# RasPi-BplusHAT.net
KiCad netlist of a schematic drawn in EAGLE
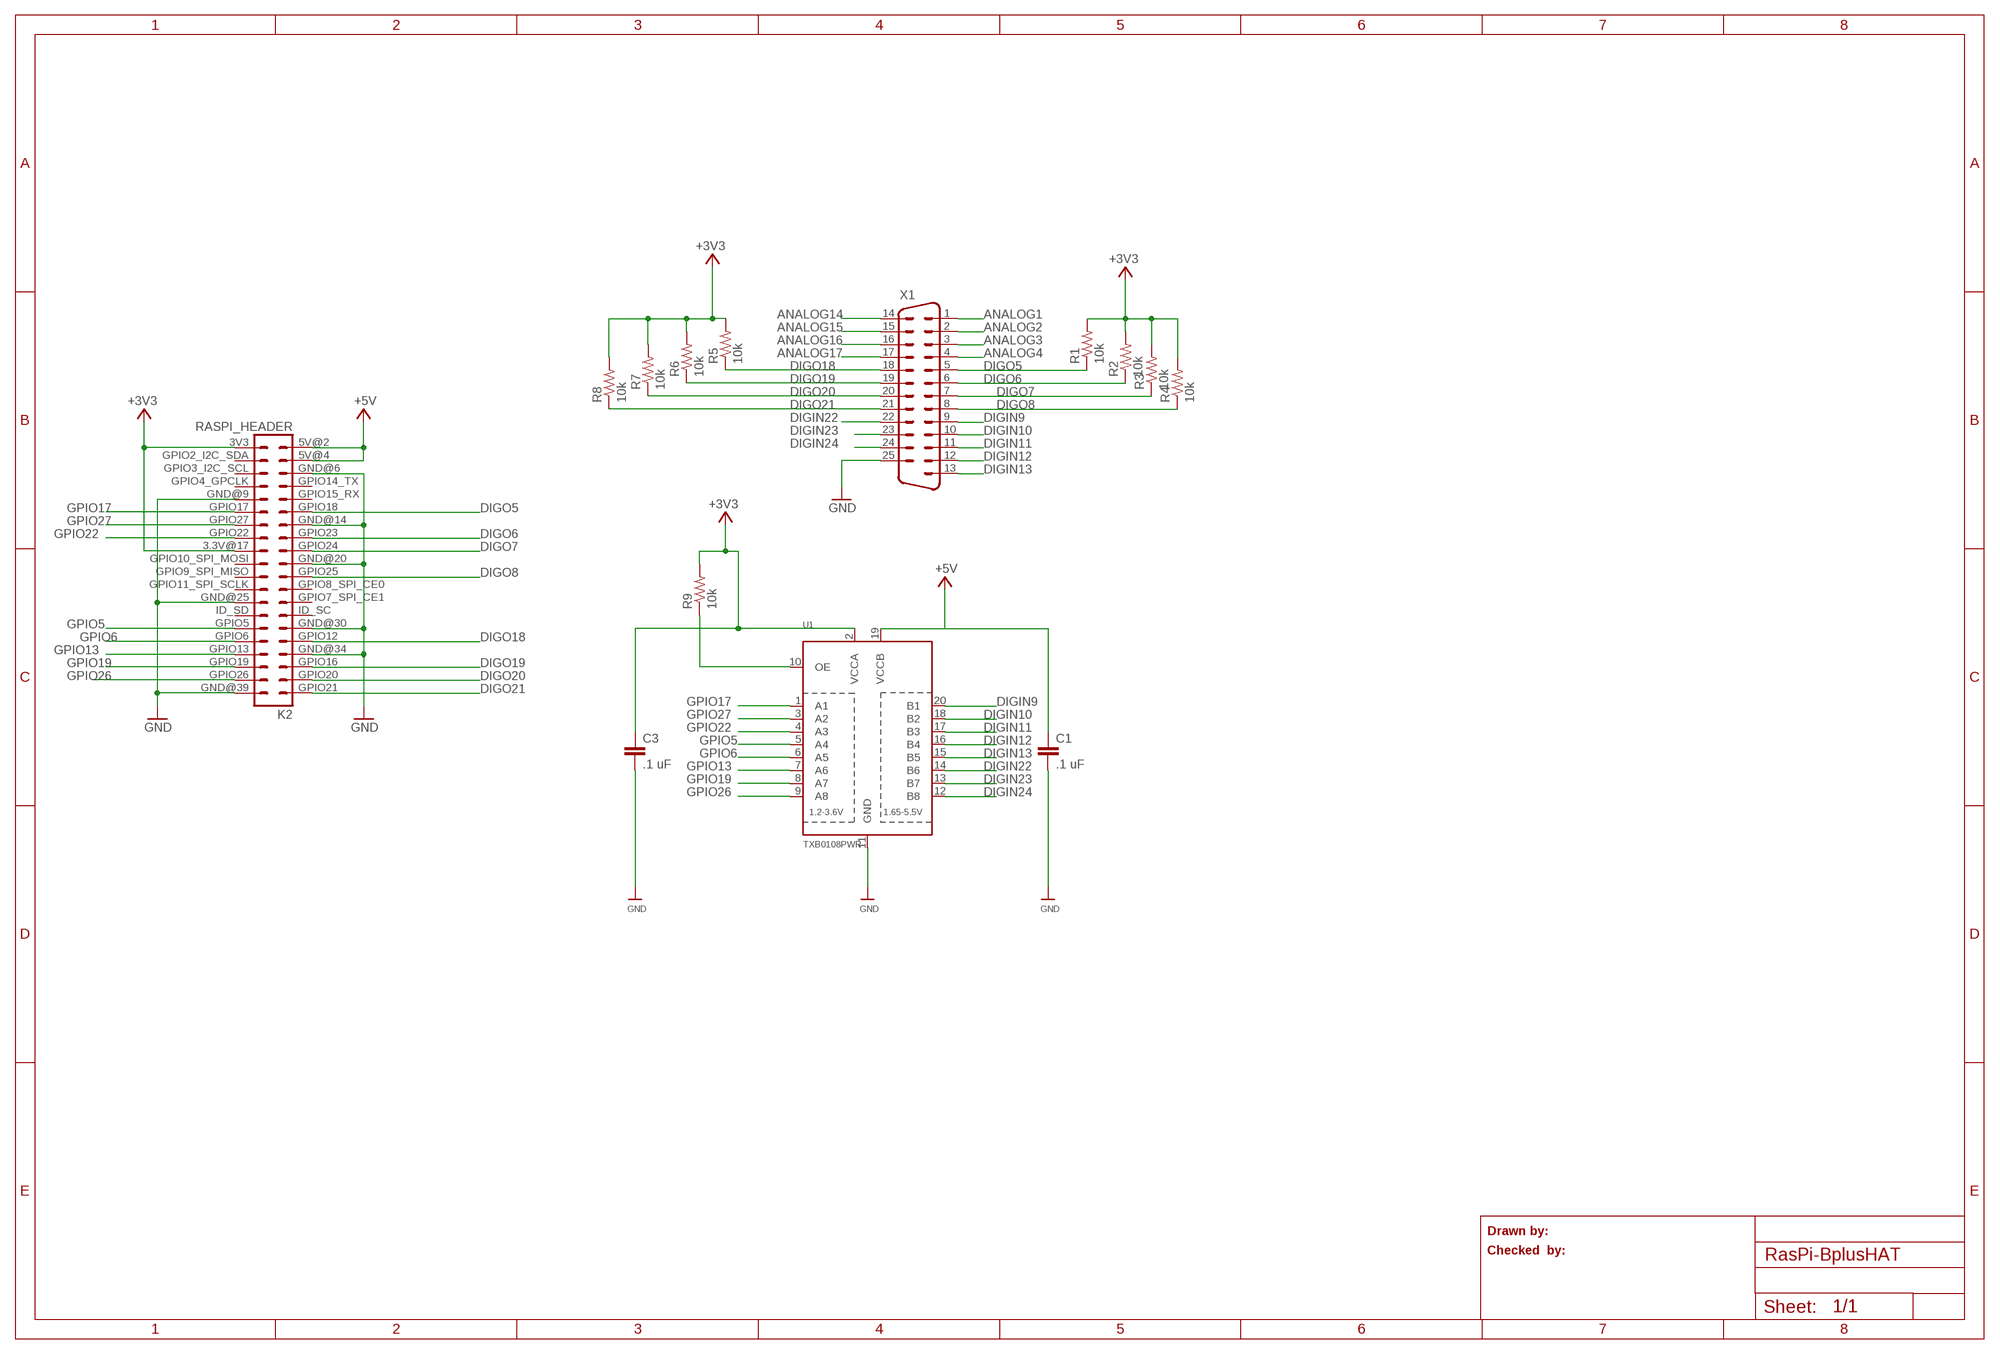
[diagram p0: schematic, sheet 1]

(export (version "E")
  (design (tool "Eeschema 10.0.6"))
  (components
    (comp (ref "C1")
      (value ".1 uF")
      (footprint "eagle-import:CAP-PTH-SMALL-KIT")
      (libsource (lib "eagle-import") (part "0.1UF-50V-20%(PTH)KIT-EZ"))
    )
    (comp (ref "C3")
      (value ".1 uF")
      (footprint "eagle-import:CAP-PTH-SMALL-KIT")
      (libsource (lib "eagle-import") (part "0.1UF-50V-20%(PTH)KIT-EZ"))
    )
    (comp (ref "K2")
      (value "RASPI_HEADER")
      (footprint "eagle-import:RASPI_HEADER")
      (libsource (lib "eagle-import") (part "RASPI_HEADER"))
    )
    (comp (ref "R1")
      (value "10k")
      (footprint "eagle-import:0207_10")
      (libsource (lib "eagle-import") (part "R-US_0207/10"))
    )
    (comp (ref "R2")
      (value "10k")
      (footprint "eagle-import:0207_10")
      (libsource (lib "eagle-import") (part "R-US_0207/10"))
    )
    (comp (ref "R3")
      (value "10k")
      (footprint "eagle-import:0207_10")
      (libsource (lib "eagle-import") (part "R-US_0207/10"))
    )
    (comp (ref "R4")
      (value "10k")
      (footprint "eagle-import:0207_10")
      (libsource (lib "eagle-import") (part "R-US_0207/10"))
    )
    (comp (ref "R5")
      (value "10k")
      (footprint "eagle-import:0207_10")
      (libsource (lib "eagle-import") (part "R-US_0207/10"))
    )
    (comp (ref "R6")
      (value "10k")
      (footprint "eagle-import:0207_10")
      (libsource (lib "eagle-import") (part "R-US_0207/10"))
    )
    (comp (ref "R7")
      (value "10k")
      (footprint "eagle-import:0207_10")
      (libsource (lib "eagle-import") (part "R-US_0207/10"))
    )
    (comp (ref "R8")
      (value "10k")
      (footprint "eagle-import:0207_10")
      (libsource (lib "eagle-import") (part "R-US_0207/10"))
    )
    (comp (ref "R9")
      (value "10k")
      (footprint "eagle-import:0207_10")
      (libsource (lib "eagle-import") (part "R-US_0207/10"))
    )
    (comp (ref "U1")
      (value "TXB0108PWR")
      (footprint "eagle-import:TSSOP20")
      (libsource (lib "eagle-import") (part "TXB0108PWR"))
    )
    (comp (ref "X1")
      (value "M25HP")
      (footprint "eagle-import:M25HP")
      (libsource (lib "eagle-import") (part "M25HP"))
    )
  )
  (nets
    (net (code "1") (name "+3V3") (class "Default")
      (node (ref "C3") (pin "1") (pinfunction "1_1") (pintype "passive"))
      (node (ref "K2") (pin "3.3V@17") (pinfunction "17_3.3V@17") (pintype "passive"))
      (node (ref "K2") (pin "3V3") (pinfunction "1_3V3") (pintype "passive"))
      (node (ref "R1") (pin "2") (pinfunction "2_2") (pintype "passive"))
      (node (ref "R2") (pin "2") (pinfunction "2_2") (pintype "passive"))
      (node (ref "R3") (pin "2") (pinfunction "2_2") (pintype "passive"))
      (node (ref "R4") (pin "2") (pinfunction "2_2") (pintype "passive"))
      (node (ref "R5") (pin "2") (pinfunction "2_2") (pintype "passive"))
      (node (ref "R6") (pin "2") (pinfunction "2_2") (pintype "passive"))
      (node (ref "R7") (pin "2") (pinfunction "2_2") (pintype "passive"))
      (node (ref "R8") (pin "2") (pinfunction "2_2") (pintype "passive"))
      (node (ref "R9") (pin "2") (pinfunction "2_2") (pintype "passive"))
      (node (ref "U1") (pin "2") (pinfunction "VCCA_2") (pintype "bidirectional"))
    )
    (net (code "2") (name "+5V") (class "Default")
      (node (ref "C1") (pin "1") (pinfunction "1_1") (pintype "passive"))
      (node (ref "K2") (pin "5V@2") (pinfunction "2_5V@2") (pintype "passive"))
      (node (ref "K2") (pin "5V@4") (pinfunction "4_5V@4") (pintype "passive"))
      (node (ref "U1") (pin "19") (pinfunction "VCCB_19") (pintype "bidirectional"))
    )
    (net (code "3") (name "/ANALOG1") (class "Default")
      (node (ref "X1") (pin "1") (pinfunction "1_1") (pintype "passive"))
    )
    (net (code "4") (name "/ANALOG2") (class "Default")
      (node (ref "X1") (pin "2") (pinfunction "2_2") (pintype "passive"))
    )
    (net (code "5") (name "/ANALOG3") (class "Default")
      (node (ref "X1") (pin "3") (pinfunction "3_3") (pintype "passive"))
    )
    (net (code "6") (name "/ANALOG4") (class "Default")
      (node (ref "X1") (pin "4") (pinfunction "4_4") (pintype "passive"))
    )
    (net (code "7") (name "/ANALOG14") (class "Default")
      (node (ref "X1") (pin "14") (pinfunction "14_14") (pintype "passive"))
    )
    (net (code "8") (name "/ANALOG15") (class "Default")
      (node (ref "X1") (pin "15") (pinfunction "15_15") (pintype "passive"))
    )
    (net (code "9") (name "/ANALOG16") (class "Default")
      (node (ref "X1") (pin "16") (pinfunction "16_16") (pintype "passive"))
    )
    (net (code "10") (name "/ANALOG17") (class "Default")
      (node (ref "X1") (pin "17") (pinfunction "17_17") (pintype "passive"))
    )
    (net (code "11") (name "/DIGIN9") (class "Default")
      (node (ref "U1") (pin "20") (pinfunction "B1_20") (pintype "bidirectional"))
      (node (ref "X1") (pin "9") (pinfunction "9_9") (pintype "passive"))
    )
    (net (code "12") (name "/DIGIN10") (class "Default")
      (node (ref "U1") (pin "18") (pinfunction "B2_18") (pintype "bidirectional"))
      (node (ref "X1") (pin "10") (pinfunction "10_10") (pintype "passive"))
    )
    (net (code "13") (name "/DIGIN11") (class "Default")
      (node (ref "U1") (pin "17") (pinfunction "B3_17") (pintype "bidirectional"))
      (node (ref "X1") (pin "11") (pinfunction "11_11") (pintype "passive"))
    )
    (net (code "14") (name "/DIGIN12") (class "Default")
      (node (ref "U1") (pin "16") (pinfunction "B4_16") (pintype "bidirectional"))
      (node (ref "X1") (pin "12") (pinfunction "12_12") (pintype "passive"))
    )
    (net (code "15") (name "/DIGIN13") (class "Default")
      (node (ref "U1") (pin "15") (pinfunction "B5_15") (pintype "bidirectional"))
      (node (ref "X1") (pin "13") (pinfunction "13_13") (pintype "passive"))
    )
    (net (code "16") (name "/DIGIN22") (class "Default")
      (node (ref "U1") (pin "14") (pinfunction "B6_14") (pintype "bidirectional"))
      (node (ref "X1") (pin "22") (pinfunction "22_22") (pintype "passive"))
    )
    (net (code "17") (name "/DIGIN23") (class "Default")
      (node (ref "U1") (pin "13") (pinfunction "B7_13") (pintype "bidirectional"))
      (node (ref "X1") (pin "23") (pinfunction "23_23") (pintype "passive"))
    )
    (net (code "18") (name "/DIGIN24") (class "Default")
      (node (ref "U1") (pin "12") (pinfunction "B8_12") (pintype "bidirectional"))
      (node (ref "X1") (pin "24") (pinfunction "24_24") (pintype "passive"))
    )
    (net (code "19") (name "/DIGO5") (class "Default")
      (node (ref "K2") (pin "GPIO18") (pinfunction "12_GPIO18") (pintype "passive"))
      (node (ref "R1") (pin "1") (pinfunction "1_1") (pintype "passive"))
      (node (ref "X1") (pin "5") (pinfunction "5_5") (pintype "passive"))
    )
    (net (code "20") (name "/DIGO6") (class "Default")
      (node (ref "K2") (pin "GPIO23") (pinfunction "16_GPIO23") (pintype "passive"))
      (node (ref "R2") (pin "1") (pinfunction "1_1") (pintype "passive"))
      (node (ref "X1") (pin "6") (pinfunction "6_6") (pintype "passive"))
    )
    (net (code "21") (name "/DIGO7") (class "Default")
      (node (ref "K2") (pin "GPIO24") (pinfunction "18_GPIO24") (pintype "passive"))
      (node (ref "R3") (pin "1") (pinfunction "1_1") (pintype "passive"))
      (node (ref "X1") (pin "7") (pinfunction "7_7") (pintype "passive"))
    )
    (net (code "22") (name "/DIGO8") (class "Default")
      (node (ref "K2") (pin "GPIO25") (pinfunction "22_GPIO25") (pintype "passive"))
      (node (ref "R4") (pin "1") (pinfunction "1_1") (pintype "passive"))
      (node (ref "X1") (pin "8") (pinfunction "8_8") (pintype "passive"))
    )
    (net (code "23") (name "/DIGO18") (class "Default")
      (node (ref "K2") (pin "GPIO12") (pinfunction "32_GPIO12") (pintype "passive"))
      (node (ref "R5") (pin "1") (pinfunction "1_1") (pintype "passive"))
      (node (ref "X1") (pin "18") (pinfunction "18_18") (pintype "passive"))
    )
    (net (code "24") (name "/DIGO19") (class "Default")
      (node (ref "K2") (pin "GPIO16") (pinfunction "36_GPIO16") (pintype "passive"))
      (node (ref "R6") (pin "1") (pinfunction "1_1") (pintype "passive"))
      (node (ref "X1") (pin "19") (pinfunction "19_19") (pintype "passive"))
    )
    (net (code "25") (name "/DIGO20") (class "Default")
      (node (ref "K2") (pin "GPIO20") (pinfunction "38_GPIO20") (pintype "passive"))
      (node (ref "R7") (pin "1") (pinfunction "1_1") (pintype "passive"))
      (node (ref "X1") (pin "20") (pinfunction "20_20") (pintype "passive"))
    )
    (net (code "26") (name "/DIGO21") (class "Default")
      (node (ref "K2") (pin "GPIO21") (pinfunction "GPIO21_GPIO21") (pintype "passive"))
      (node (ref "R8") (pin "1") (pinfunction "1_1") (pintype "passive"))
      (node (ref "X1") (pin "21") (pinfunction "21_21") (pintype "passive"))
    )
    (net (code "27") (name "/GPIO5") (class "Default")
      (node (ref "K2") (pin "GPIO5") (pinfunction "29_GPIO5") (pintype "passive"))
      (node (ref "U1") (pin "5") (pinfunction "A4_5") (pintype "bidirectional"))
    )
    (net (code "28") (name "/GPIO6") (class "Default")
      (node (ref "K2") (pin "GPIO6") (pinfunction "31_GPIO6") (pintype "passive"))
      (node (ref "U1") (pin "6") (pinfunction "A5_6") (pintype "bidirectional"))
    )
    (net (code "29") (name "/GPIO13") (class "Default")
      (node (ref "K2") (pin "GPIO13") (pinfunction "33_GPIO13") (pintype "passive"))
      (node (ref "U1") (pin "7") (pinfunction "A6_7") (pintype "bidirectional"))
    )
    (net (code "30") (name "/GPIO17") (class "Default")
      (node (ref "K2") (pin "GPIO17") (pinfunction "11_GPIO17") (pintype "passive"))
      (node (ref "U1") (pin "1") (pinfunction "A1_1") (pintype "bidirectional"))
    )
    (net (code "31") (name "/GPIO19") (class "Default")
      (node (ref "K2") (pin "GPIO19") (pinfunction "35_GPIO19") (pintype "passive"))
      (node (ref "U1") (pin "8") (pinfunction "A7_8") (pintype "bidirectional"))
    )
    (net (code "32") (name "/GPIO22") (class "Default")
      (node (ref "K2") (pin "GPIO22") (pinfunction "15_GPIO22") (pintype "passive"))
      (node (ref "U1") (pin "4") (pinfunction "A3_4") (pintype "bidirectional"))
    )
    (net (code "33") (name "/GPIO26") (class "Default")
      (node (ref "K2") (pin "GPIO26") (pinfunction "37_GPIO26") (pintype "passive"))
      (node (ref "U1") (pin "9") (pinfunction "A8_9") (pintype "bidirectional"))
    )
    (net (code "34") (name "/GPIO27") (class "Default")
      (node (ref "K2") (pin "GPIO27") (pinfunction "13_GPIO27") (pintype "passive"))
      (node (ref "U1") (pin "3") (pinfunction "A2_3") (pintype "bidirectional"))
    )
    (net (code "35") (name "GND") (class "Default")
      (node (ref "C1") (pin "2") (pinfunction "2_2") (pintype "passive"))
      (node (ref "C3") (pin "2") (pinfunction "2_2") (pintype "passive"))
      (node (ref "K2") (pin "GND@14") (pinfunction "14_GND@14") (pintype "passive"))
      (node (ref "K2") (pin "GND@20") (pinfunction "20_GND@20") (pintype "passive"))
      (node (ref "K2") (pin "GND@25") (pinfunction "25_GND@25") (pintype "passive"))
      (node (ref "K2") (pin "GND@30") (pinfunction "30_GND@30") (pintype "passive"))
      (node (ref "K2") (pin "GND@34") (pinfunction "34_GND@34") (pintype "passive"))
      (node (ref "K2") (pin "GND@39") (pinfunction "39_GND@39") (pintype "passive"))
      (node (ref "K2") (pin "GND@6") (pinfunction "6_GND@6") (pintype "passive"))
      (node (ref "K2") (pin "GND@9") (pinfunction "9_GND@9") (pintype "passive"))
      (node (ref "U1") (pin "11") (pinfunction "GND_11") (pintype "bidirectional"))
      (node (ref "X1") (pin "25") (pinfunction "25_25") (pintype "passive"))
    )
    (net (code "36") (name "Net-(U1-OE)") (class "Default")
      (node (ref "R9") (pin "1") (pinfunction "1_1") (pintype "passive"))
      (node (ref "U1") (pin "10") (pinfunction "OE_10") (pintype "bidirectional"))
    )
    (net (code "37") (name "unconnected-(K2-3-PadGPIO2_I2C_SDA)") (class "Default")
      (node (ref "K2") (pin "GPIO2_I2C_SDA") (pinfunction "3_GPIO2_I2C_SDA") (pintype "passive"))
    )
    (net (code "38") (name "unconnected-(K2-5-PadGPIO3_I2C_SCL)") (class "Default")
      (node (ref "K2") (pin "GPIO3_I2C_SCL") (pinfunction "5_GPIO3_I2C_SCL") (pintype "passive"))
    )
    (net (code "39") (name "unconnected-(K2-7-PadGPIO4_GPCLK)") (class "Default")
      (node (ref "K2") (pin "GPIO4_GPCLK") (pinfunction "7_GPIO4_GPCLK") (pintype "passive"))
    )
    (net (code "40") (name "unconnected-(K2-8-PadGPIO14_TX)") (class "Default")
      (node (ref "K2") (pin "GPIO14_TX") (pinfunction "8_GPIO14_TX") (pintype "passive"))
    )
    (net (code "41") (name "unconnected-(K2-10-PadGPIO15_RX)") (class "Default")
      (node (ref "K2") (pin "GPIO15_RX") (pinfunction "10_GPIO15_RX") (pintype "passive"))
    )
    (net (code "42") (name "unconnected-(K2-19-PadGPIO10_SPI_MOSI)") (class "Default")
      (node (ref "K2") (pin "GPIO10_SPI_MOSI") (pinfunction "19_GPIO10_SPI_MOSI") (pintype "passive"))
    )
    (net (code "43") (name "unconnected-(K2-21-PadGPIO9_SPI_MISO)") (class "Default")
      (node (ref "K2") (pin "GPIO9_SPI_MISO") (pinfunction "21_GPIO9_SPI_MISO") (pintype "passive"))
    )
    (net (code "44") (name "unconnected-(K2-23-PadGPIO11_SPI_SCLK)") (class "Default")
      (node (ref "K2") (pin "GPIO11_SPI_SCLK") (pinfunction "23_GPIO11_SPI_SCLK") (pintype "passive"))
    )
    (net (code "45") (name "unconnected-(K2-24-PadGPIO8_SPI_CE0)") (class "Default")
      (node (ref "K2") (pin "GPIO8_SPI_CE0") (pinfunction "24_GPIO8_SPI_CE0") (pintype "passive"))
    )
    (net (code "46") (name "unconnected-(K2-26-PadGPIO7_SPI_CE1)") (class "Default")
      (node (ref "K2") (pin "GPIO7_SPI_CE1") (pinfunction "26_GPIO7_SPI_CE1") (pintype "passive"))
    )
    (net (code "47") (name "unconnected-(K2-27-PadID_SD)") (class "Default")
      (node (ref "K2") (pin "ID_SD") (pinfunction "27_ID_SD") (pintype "passive"))
    )
    (net (code "48") (name "unconnected-(K2-28-PadID_SC)") (class "Default")
      (node (ref "K2") (pin "ID_SC") (pinfunction "28_ID_SC") (pintype "passive"))
    )
  )
)
